# Sheet1.net
KiCad netlist of a schematic drawn in Altium Designer
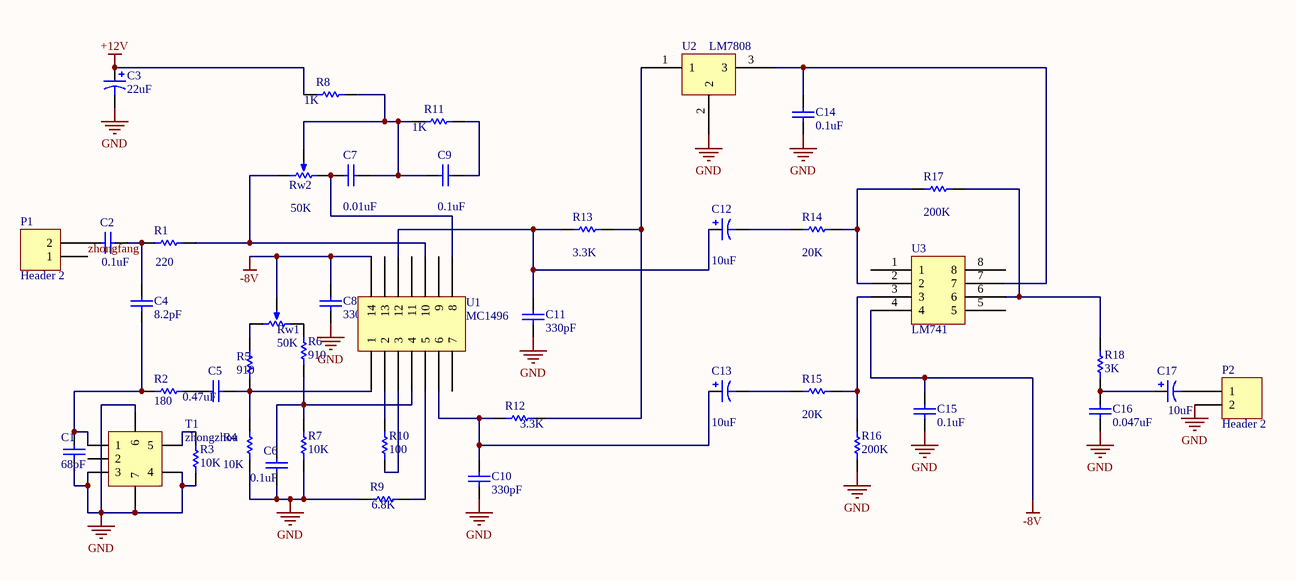
[diagram p0: Sheet1.SchDoc]

(export (version "E")
  (design (tool "Eeschema 10.0.6"))
  (components
    (comp (ref "C1")
      (value "68pF")
      (footprint "2012[0805]")
      (description "Capacitor")
      (fields (field (name "Comment") "Cap") (field (name "PUBLISHER") "Altium Limited"))
      (libsource (lib "Miscellaneous Devices") (part "Cap"))
    )
    (comp (ref "C2")
      (value "0.1uF")
      (footprint "2012[0805]")
      (description "Capacitor")
      (fields (field (name "Comment") "Cap") (field (name "PUBLISHER") "Altium Limited"))
      (libsource (lib "Miscellaneous Devices") (part "Cap"))
    )
    (comp (ref "C3")
      (value "22uF")
      (footprint "C1206")
      (description "Polarized Capacitor (Radial)")
      (fields (field (name "Comment") "Cap Pol1") (field (name "PUBLISHER") "Altium Limited"))
      (libsource (lib "Miscellaneous Devices") (part "Cap Pol1"))
    )
    (comp (ref "C4")
      (value "8.2pF")
      (footprint "2012[0805]")
      (description "Capacitor")
      (fields (field (name "Comment") "Cap") (field (name "PUBLISHER") "Altium Limited"))
      (libsource (lib "Miscellaneous Devices") (part "Cap"))
    )
    (comp (ref "C5")
      (value "0.47uF")
      (footprint "2012[0805]")
      (description "Capacitor")
      (fields (field (name "Comment") "Cap") (field (name "PUBLISHER") "Altium Limited"))
      (libsource (lib "Miscellaneous Devices") (part "Cap"))
    )
    (comp (ref "C6")
      (value "0.1uF")
      (footprint "2012[0805]")
      (description "Capacitor")
      (fields (field (name "Comment") "Cap") (field (name "PUBLISHER") "Altium Limited"))
      (libsource (lib "Miscellaneous Devices") (part "Cap"))
    )
    (comp (ref "C7")
      (value "0.01uF")
      (footprint "2012[0805]")
      (description "Capacitor")
      (fields (field (name "Comment") "Cap") (field (name "PUBLISHER") "Altium Limited"))
      (libsource (lib "Miscellaneous Devices") (part "Cap"))
    )
    (comp (ref "C8")
      (value "330pF")
      (footprint "2012[0805]")
      (description "Capacitor")
      (fields (field (name "Comment") "Cap") (field (name "PUBLISHER") "Altium Limited"))
      (libsource (lib "Miscellaneous Devices") (part "Cap"))
    )
    (comp (ref "C9")
      (value "0.1uF")
      (footprint "2012[0805]")
      (description "Capacitor")
      (fields (field (name "Comment") "Cap") (field (name "PUBLISHER") "Altium Limited"))
      (libsource (lib "Miscellaneous Devices") (part "Cap"))
    )
    (comp (ref "C10")
      (value "330pF")
      (footprint "2012[0805]")
      (description "Capacitor")
      (fields (field (name "Comment") "Cap") (field (name "PUBLISHER") "Altium Limited"))
      (libsource (lib "Miscellaneous Devices") (part "Cap"))
    )
    (comp (ref "C11")
      (value "330pF")
      (footprint "2012[0805]")
      (description "Capacitor")
      (fields (field (name "Comment") "Cap") (field (name "PUBLISHER") "Altium Limited"))
      (libsource (lib "Miscellaneous Devices") (part "Cap"))
    )
    (comp (ref "C12")
      (value "10uF")
      (footprint "C1206")
      (description "Polarized Capacitor (Radial)")
      (fields (field (name "Comment") "Cap Pol1") (field (name "PUBLISHER") "Altium Limited"))
      (libsource (lib "Miscellaneous Devices") (part "Cap Pol1"))
    )
    (comp (ref "C13")
      (value "10uF")
      (footprint "C1206")
      (description "Polarized Capacitor (Radial)")
      (fields (field (name "Comment") "Cap Pol1") (field (name "PUBLISHER") "Altium Limited"))
      (libsource (lib "Miscellaneous Devices") (part "Cap Pol1"))
    )
    (comp (ref "C14")
      (value "0.1uF")
      (footprint "2012[0805]")
      (description "Capacitor")
      (fields (field (name "Comment") "Cap") (field (name "PUBLISHER") "Altium Limited"))
      (libsource (lib "Miscellaneous Devices") (part "Cap"))
    )
    (comp (ref "C15")
      (value "0.1uF")
      (footprint "2012[0805]")
      (description "Capacitor")
      (fields (field (name "Comment") "Cap") (field (name "PUBLISHER") "Altium Limited"))
      (libsource (lib "Miscellaneous Devices") (part "Cap"))
    )
    (comp (ref "C16")
      (value "0.047uF")
      (footprint "2012[0805]")
      (description "Capacitor")
      (fields (field (name "Comment") "Cap") (field (name "PUBLISHER") "Altium Limited"))
      (libsource (lib "Miscellaneous Devices") (part "Cap"))
    )
    (comp (ref "C17")
      (value "10uF")
      (footprint "C1206")
      (description "Polarized Capacitor (Radial)")
      (fields (field (name "Comment") "Cap Pol1") (field (name "PUBLISHER") "Altium Limited"))
      (libsource (lib "Miscellaneous Devices") (part "Cap Pol1"))
    )
    (comp (ref "P1")
      (value "Header 2")
      (footprint "HDR1X2")
      (description "Header, 2-Pin")
      (fields (field (name "PUBLISHER") "Altium Limited"))
      (libsource (lib "") (part "Header 2_1"))
    )
    (comp (ref "P2")
      (value "Header 2")
      (footprint "HDR1X2")
      (description "Header, 2-Pin")
      (fields (field (name "PUBLISHER") "Altium Limited"))
      (libsource (lib "Miscellaneous Connectors") (part "Header 2"))
    )
    (comp (ref "R1")
      (value "220")
      (footprint "2012[0805]")
      (description "Resistor")
      (fields (field (name "Comment") "Res1") (field (name "PUBLISHER") "Altium Limited"))
      (libsource (lib "Miscellaneous Devices") (part "Res1"))
    )
    (comp (ref "R2")
      (value "180")
      (footprint "2012[0805]")
      (description "Resistor")
      (fields (field (name "Comment") "Res1") (field (name "PUBLISHER") "Altium Limited"))
      (libsource (lib "Miscellaneous Devices") (part "Res1"))
    )
    (comp (ref "R3")
      (value "10K")
      (footprint "2012[0805]")
      (description "Resistor")
      (fields (field (name "Comment") "Res1") (field (name "PUBLISHER") "Altium Limited"))
      (libsource (lib "Miscellaneous Devices") (part "Res1"))
    )
    (comp (ref "R4")
      (value "10K")
      (footprint "2012[0805]")
      (description "Resistor")
      (fields (field (name "Comment") "Res1") (field (name "PUBLISHER") "Altium Limited"))
      (libsource (lib "Miscellaneous Devices") (part "Res1"))
    )
    (comp (ref "R5")
      (value "910")
      (footprint "2012[0805]")
      (description "Resistor")
      (fields (field (name "Comment") "Res1") (field (name "PUBLISHER") "Altium Limited"))
      (libsource (lib "Miscellaneous Devices") (part "Res1"))
    )
    (comp (ref "R6")
      (value "910")
      (footprint "2012[0805]")
      (description "Resistor")
      (fields (field (name "Comment") "Res1") (field (name "PUBLISHER") "Altium Limited"))
      (libsource (lib "Miscellaneous Devices") (part "Res1"))
    )
    (comp (ref "R7")
      (value "10K")
      (footprint "2012[0805]")
      (description "Resistor")
      (fields (field (name "Comment") "Res1") (field (name "PUBLISHER") "Altium Limited"))
      (libsource (lib "Miscellaneous Devices") (part "Res1"))
    )
    (comp (ref "R8")
      (value "1K")
      (footprint "2012[0805]")
      (description "Resistor")
      (fields (field (name "Comment") "Res1") (field (name "PUBLISHER") "Altium Limited"))
      (libsource (lib "Miscellaneous Devices") (part "Res1"))
    )
    (comp (ref "R9")
      (value "6.8K")
      (footprint "2012[0805]")
      (description "Resistor")
      (fields (field (name "Comment") "Res1") (field (name "PUBLISHER") "Altium Limited"))
      (libsource (lib "Miscellaneous Devices") (part "Res1"))
    )
    (comp (ref "R10")
      (value "100")
      (footprint "2012[0805]")
      (description "Resistor")
      (fields (field (name "Comment") "Res1") (field (name "PUBLISHER") "Altium Limited"))
      (libsource (lib "Miscellaneous Devices") (part "Res1"))
    )
    (comp (ref "R11")
      (value "1K")
      (footprint "2012[0805]")
      (description "Resistor")
      (fields (field (name "Comment") "Res1") (field (name "PUBLISHER") "Altium Limited"))
      (libsource (lib "Miscellaneous Devices") (part "Res1"))
    )
    (comp (ref "R12")
      (value "3.3K")
      (footprint "2012[0805]")
      (description "Resistor")
      (fields (field (name "Comment") "Res1") (field (name "PUBLISHER") "Altium Limited"))
      (libsource (lib "Miscellaneous Devices") (part "Res1"))
    )
    (comp (ref "R13")
      (value "3.3K")
      (footprint "2012[0805]")
      (description "Resistor")
      (fields (field (name "Comment") "Res1") (field (name "PUBLISHER") "Altium Limited"))
      (libsource (lib "Miscellaneous Devices") (part "Res1"))
    )
    (comp (ref "R14")
      (value "20K")
      (footprint "2012[0805]")
      (description "Resistor")
      (fields (field (name "Comment") "Res1") (field (name "PUBLISHER") "Altium Limited"))
      (libsource (lib "Miscellaneous Devices") (part "Res1"))
    )
    (comp (ref "R15")
      (value "20K")
      (footprint "2012[0805]")
      (description "Resistor")
      (fields (field (name "Comment") "Res1") (field (name "PUBLISHER") "Altium Limited"))
      (libsource (lib "Miscellaneous Devices") (part "Res1"))
    )
    (comp (ref "R16")
      (value "200K")
      (footprint "2012[0805]")
      (description "Resistor")
      (fields (field (name "Comment") "Res1") (field (name "PUBLISHER") "Altium Limited"))
      (libsource (lib "Miscellaneous Devices") (part "Res1"))
    )
    (comp (ref "R17")
      (value "200K")
      (footprint "2012[0805]")
      (description "Resistor")
      (fields (field (name "Comment") "Res1") (field (name "PUBLISHER") "Altium Limited"))
      (libsource (lib "Miscellaneous Devices") (part "Res1"))
    )
    (comp (ref "R18")
      (value "3K")
      (footprint "2012[0805]")
      (description "Resistor")
      (fields (field (name "Comment") "Res1") (field (name "PUBLISHER") "Altium Limited"))
      (libsource (lib "Miscellaneous Devices") (part "Res1"))
    )
    (comp (ref "Rw1")
      (value "50K")
      (footprint "VR5")
      (description "Potentiometer")
      (fields (field (name "Comment") "RPot") (field (name "PUBLISHER") "Altium Limited"))
      (libsource (lib "Miscellaneous Devices") (part "RPot"))
    )
    (comp (ref "Rw2")
      (value "50K")
      (footprint "VR5")
      (description "Potentiometer")
      (fields (field (name "Comment") "RPot") (field (name "PUBLISHER") "Altium Limited"))
      (libsource (lib "Miscellaneous Devices") (part "RPot"))
    )
    (comp (ref "T1")
      (value "zhongzhou")
      (footprint "zhongzhou")
      (libsource (lib "Schlib1") (part "zhongzhou"))
    )
    (comp (ref "U1") (value "MC1496") (footprint "MC1496") (libsource (lib "Schlib1") (part "MC1496")))
    (comp (ref "U2") (value "LM7808") (footprint "LM7808") (libsource (lib "Schlib1") (part "LM7808")))
    (comp (ref "U3") (value "LM741") (footprint "LM741") (libsource (lib "Schlib1") (part "LM741")))
  )
  (nets
    (net (code "1") (name "+12V") (class "Default")
      (node (ref "C3") (pin "1") (pinfunction "1_1") (pintype "passive"))
      (node (ref "R8") (pin "1") (pinfunction "1_1") (pintype "passive"))
    )
    (net (code "2") (name "-8V") (class "Default")
      (node (ref "C15") (pin "2") (pinfunction "2_2") (pintype "passive"))
      (node (ref "C8") (pin "2") (pinfunction "2_2") (pintype "passive"))
      (node (ref "Rw1") (pin "3") (pinfunction "TAP_3") (pintype "passive"))
      (node (ref "U1") (pin "14") (pinfunction "14_14") (pintype "passive"))
      (node (ref "U3") (pin "4") (pinfunction "4_4") (pintype "passive"))
    )
    (net (code "3") (name "/zhongfang") (class "Default")
      (node (ref "P1") (pin "1") (pinfunction "1_1") (pintype "passive"))
    )
    (net (code "4") (name "GND") (class "Default")
      (node (ref "C1") (pin "1") (pinfunction "1_1") (pintype "passive"))
      (node (ref "C10") (pin "1") (pinfunction "1_1") (pintype "passive"))
      (node (ref "C11") (pin "1") (pinfunction "1_1") (pintype "passive"))
      (node (ref "C14") (pin "1") (pinfunction "1_1") (pintype "passive"))
      (node (ref "C15") (pin "1") (pinfunction "1_1") (pintype "passive"))
      (node (ref "C16") (pin "1") (pinfunction "1_1") (pintype "passive"))
      (node (ref "C3") (pin "2") (pinfunction "2_2") (pintype "passive"))
      (node (ref "C6") (pin "1") (pinfunction "1_1") (pintype "passive"))
      (node (ref "C8") (pin "1") (pinfunction "1_1") (pintype "passive"))
      (node (ref "P2") (pin "2") (pinfunction "2_2") (pintype "passive"))
      (node (ref "R16") (pin "1") (pinfunction "1_1") (pintype "passive"))
      (node (ref "R3") (pin "1") (pinfunction "1_1") (pintype "passive"))
      (node (ref "R4") (pin "1") (pinfunction "1_1") (pintype "passive"))
      (node (ref "R7") (pin "1") (pinfunction "1_1") (pintype "passive"))
      (node (ref "R9") (pin "1") (pinfunction "1_1") (pintype "passive"))
      (node (ref "T1") (pin "3") (pinfunction "3_3") (pintype "passive"))
      (node (ref "T1") (pin "4") (pinfunction "4_4") (pintype "passive"))
      (node (ref "T1") (pin "6") (pinfunction "6_6") (pintype "passive"))
      (node (ref "T1") (pin "7") (pinfunction "7_7") (pintype "passive"))
      (node (ref "U2") (pin "2") (pinfunction "2_2") (pintype "passive"))
    )
    (net (code "5") (name "Net-(C1-Pad2)") (class "Default")
      (node (ref "C1") (pin "2") (pinfunction "2_2") (pintype "passive"))
      (node (ref "C4") (pin "1") (pinfunction "1_1") (pintype "passive"))
      (node (ref "R2") (pin "1") (pinfunction "1_1") (pintype "passive"))
      (node (ref "T1") (pin "1") (pinfunction "1_1") (pintype "passive"))
    )
    (net (code "6") (name "Net-(C2-Pad1)") (class "Default")
      (node (ref "C2") (pin "1") (pinfunction "1_1") (pintype "passive"))
      (node (ref "P1") (pin "2") (pinfunction "2_2") (pintype "passive"))
    )
    (net (code "7") (name "Net-(C2-Pad2)") (class "Default")
      (node (ref "C2") (pin "2") (pinfunction "2_2") (pintype "passive"))
      (node (ref "C4") (pin "2") (pinfunction "2_2") (pintype "passive"))
      (node (ref "R1") (pin "1") (pinfunction "1_1") (pintype "passive"))
    )
    (net (code "8") (name "Net-(C5-Pad1)") (class "Default")
      (node (ref "C5") (pin "1") (pinfunction "1_1") (pintype "passive"))
      (node (ref "R2") (pin "2") (pinfunction "2_2") (pintype "passive"))
    )
    (net (code "9") (name "Net-(C5-Pad2)") (class "Default")
      (node (ref "C5") (pin "2") (pinfunction "2_2") (pintype "passive"))
      (node (ref "R4") (pin "2") (pinfunction "2_2") (pintype "passive"))
      (node (ref "R5") (pin "1") (pinfunction "1_1") (pintype "passive"))
      (node (ref "U1") (pin "1") (pinfunction "1_1") (pintype "passive"))
    )
    (net (code "10") (name "Net-(C6-Pad2)") (class "Default")
      (node (ref "C6") (pin "2") (pinfunction "2_2") (pintype "passive"))
      (node (ref "R6") (pin "1") (pinfunction "1_1") (pintype "passive"))
      (node (ref "R7") (pin "2") (pinfunction "2_2") (pintype "passive"))
      (node (ref "U1") (pin "4") (pinfunction "4_4") (pintype "passive"))
    )
    (net (code "11") (name "Net-(C9-Pad2)") (class "Default")
      (node (ref "C9") (pin "2") (pinfunction "2_2") (pintype "passive"))
      (node (ref "R11") (pin "2") (pinfunction "2_2") (pintype "passive"))
    )
    (net (code "12") (name "Net-(C10-Pad2)") (class "Default")
      (node (ref "C10") (pin "2") (pinfunction "2_2") (pintype "passive"))
      (node (ref "C13") (pin "1") (pinfunction "1_1") (pintype "passive"))
      (node (ref "R12") (pin "1") (pinfunction "1_1") (pintype "passive"))
      (node (ref "U1") (pin "6") (pinfunction "6_6") (pintype "passive"))
    )
    (net (code "13") (name "Net-(C11-Pad2)") (class "Default")
      (node (ref "C11") (pin "2") (pinfunction "2_2") (pintype "passive"))
      (node (ref "C12") (pin "1") (pinfunction "1_1") (pintype "passive"))
      (node (ref "R13") (pin "1") (pinfunction "1_1") (pintype "passive"))
      (node (ref "U1") (pin "12") (pinfunction "12_12") (pintype "passive"))
    )
    (net (code "14") (name "Net-(C12-Pad2)") (class "Default")
      (node (ref "C12") (pin "2") (pinfunction "2_2") (pintype "passive"))
      (node (ref "R14") (pin "1") (pinfunction "1_1") (pintype "passive"))
    )
    (net (code "15") (name "Net-(C13-Pad2)") (class "Default")
      (node (ref "C13") (pin "2") (pinfunction "2_2") (pintype "passive"))
      (node (ref "R15") (pin "1") (pinfunction "1_1") (pintype "passive"))
    )
    (net (code "16") (name "Net-(C14-Pad2)") (class "Default")
      (node (ref "C14") (pin "2") (pinfunction "2_2") (pintype "passive"))
      (node (ref "U2") (pin "3") (pinfunction "3_3") (pintype "passive"))
      (node (ref "U3") (pin "7") (pinfunction "7_7") (pintype "passive"))
    )
    (net (code "17") (name "Net-(C16-Pad2)") (class "Default")
      (node (ref "C16") (pin "2") (pinfunction "2_2") (pintype "passive"))
      (node (ref "C17") (pin "1") (pinfunction "1_1") (pintype "passive"))
      (node (ref "R18") (pin "1") (pinfunction "1_1") (pintype "passive"))
    )
    (net (code "18") (name "Net-(C17-Pad2)") (class "Default")
      (node (ref "C17") (pin "2") (pinfunction "2_2") (pintype "passive"))
      (node (ref "P2") (pin "1") (pinfunction "1_1") (pintype "passive"))
    )
    (net (code "19") (name "Net-(R3-Pad2)") (class "Default")
      (node (ref "R3") (pin "2") (pinfunction "2_2") (pintype "passive"))
      (node (ref "T1") (pin "5") (pinfunction "5_5") (pintype "passive"))
    )
    (net (code "20") (name "Net-(R9-Pad2)") (class "Default")
      (node (ref "R9") (pin "2") (pinfunction "2_2") (pintype "passive"))
      (node (ref "U1") (pin "5") (pinfunction "5_5") (pintype "passive"))
    )
    (net (code "21") (name "Net-(R10-Pad1)") (class "Default")
      (node (ref "R10") (pin "1") (pinfunction "1_1") (pintype "passive"))
      (node (ref "U1") (pin "3") (pinfunction "3_3") (pintype "passive"))
    )
    (net (code "22") (name "Net-(R10-Pad2)") (class "Default")
      (node (ref "R10") (pin "2") (pinfunction "2_2") (pintype "passive"))
      (node (ref "U1") (pin "2") (pinfunction "2_2") (pintype "passive"))
    )
    (net (code "23") (name "Net-(R12-Pad2)") (class "Default")
      (node (ref "R12") (pin "2") (pinfunction "2_2") (pintype "passive"))
      (node (ref "R13") (pin "2") (pinfunction "2_2") (pintype "passive"))
      (node (ref "U2") (pin "1") (pinfunction "1_1") (pintype "passive"))
    )
    (net (code "24") (name "Net-(R14-Pad2)") (class "Default")
      (node (ref "R14") (pin "2") (pinfunction "2_2") (pintype "passive"))
      (node (ref "R17") (pin "1") (pinfunction "1_1") (pintype "passive"))
      (node (ref "U3") (pin "2") (pinfunction "2_2") (pintype "passive"))
    )
    (net (code "25") (name "Net-(R15-Pad2)") (class "Default")
      (node (ref "R15") (pin "2") (pinfunction "2_2") (pintype "passive"))
      (node (ref "R16") (pin "2") (pinfunction "2_2") (pintype "passive"))
      (node (ref "U3") (pin "3") (pinfunction "3_3") (pintype "passive"))
    )
    (net (code "26") (name "Net-(R17-Pad2)") (class "Default")
      (node (ref "R17") (pin "2") (pinfunction "2_2") (pintype "passive"))
      (node (ref "R18") (pin "2") (pinfunction "2_2") (pintype "passive"))
      (node (ref "U3") (pin "6") (pinfunction "6_6") (pintype "passive"))
    )
    (net (code "27") (name "Net-(Rw1-BOT)") (class "Default")
      (node (ref "R5") (pin "2") (pinfunction "2_2") (pintype "passive"))
      (node (ref "Rw1") (pin "2") (pinfunction "BOT_2") (pintype "passive"))
    )
    (net (code "28") (name "Net-(Rw1-TOP)") (class "Default")
      (node (ref "R6") (pin "2") (pinfunction "2_2") (pintype "passive"))
      (node (ref "Rw1") (pin "1") (pinfunction "TOP_1") (pintype "passive"))
    )
    (net (code "29") (name "Net-(Rw2-BOT)") (class "Default")
      (node (ref "R1") (pin "2") (pinfunction "2_2") (pintype "passive"))
      (node (ref "Rw2") (pin "2") (pinfunction "BOT_2") (pintype "passive"))
      (node (ref "U1") (pin "10") (pinfunction "10_10") (pintype "passive"))
    )
    (net (code "30") (name "Net-(Rw2-TAP)") (class "Default")
      (node (ref "C7") (pin "2") (pinfunction "2_2") (pintype "passive"))
      (node (ref "C9") (pin "1") (pinfunction "1_1") (pintype "passive"))
      (node (ref "R11") (pin "1") (pinfunction "1_1") (pintype "passive"))
      (node (ref "R8") (pin "2") (pinfunction "2_2") (pintype "passive"))
      (node (ref "Rw2") (pin "3") (pinfunction "TAP_3") (pintype "passive"))
    )
    (net (code "31") (name "Net-(Rw2-TOP)") (class "Default")
      (node (ref "C7") (pin "1") (pinfunction "1_1") (pintype "passive"))
      (node (ref "Rw2") (pin "1") (pinfunction "TOP_1") (pintype "passive"))
      (node (ref "U1") (pin "8") (pinfunction "8_8") (pintype "passive"))
    )
    (net (code "32") (name "unconnected-(T1-Pad2)") (class "Default")
      (node (ref "T1") (pin "2") (pinfunction "2_2") (pintype "passive"))
    )
    (net (code "33") (name "unconnected-(U1-Pad7)") (class "Default")
      (node (ref "U1") (pin "7") (pinfunction "7_7") (pintype "passive"))
    )
    (net (code "34") (name "unconnected-(U1-Pad9)") (class "Default")
      (node (ref "U1") (pin "9") (pinfunction "9_9") (pintype "passive"))
    )
    (net (code "35") (name "unconnected-(U1-Pad11)") (class "Default")
      (node (ref "U1") (pin "11") (pinfunction "11_11") (pintype "passive"))
    )
    (net (code "36") (name "unconnected-(U1-Pad13)") (class "Default")
      (node (ref "U1") (pin "13") (pinfunction "13_13") (pintype "passive"))
    )
    (net (code "37") (name "unconnected-(U3-Pad1)") (class "Default")
      (node (ref "U3") (pin "1") (pinfunction "1_1") (pintype "passive"))
    )
    (net (code "38") (name "unconnected-(U3-Pad5)") (class "Default")
      (node (ref "U3") (pin "5") (pinfunction "5_5") (pintype "passive"))
    )
    (net (code "39") (name "unconnected-(U3-Pad8)") (class "Default")
      (node (ref "U3") (pin "8") (pinfunction "8_8") (pintype "passive"))
    )
  )
)
